# HVsense.net
KiCad netlist of a schematic drawn in Altium Designer
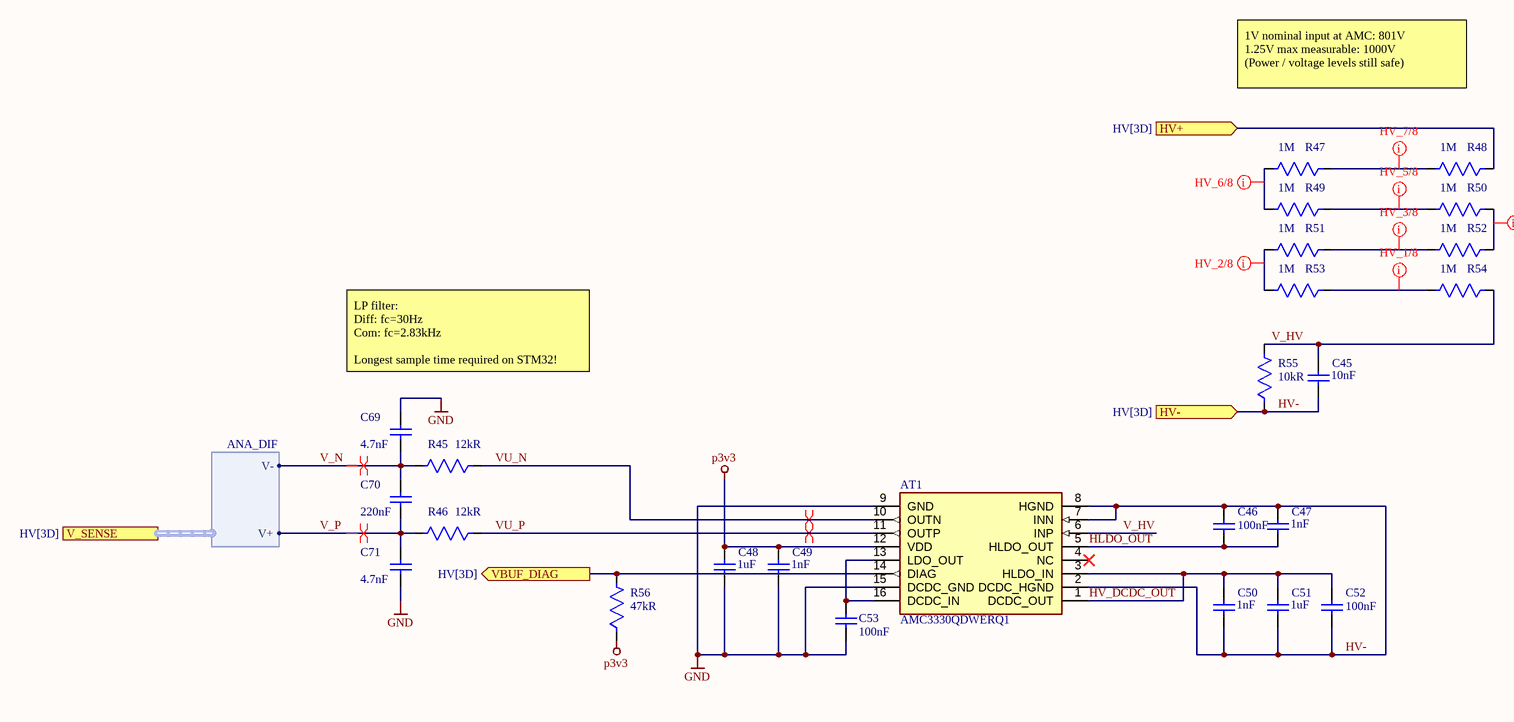
[diagram p0: HVsense.SchDoc]

(export (version "E")
  (design (tool "Eeschema 10.0.6"))
  (components
    (comp (ref "AT1")
      (value "AMC3330QDWERQ1")
      (footprint "SOIC127P1030X265-16N")
      (description "Attenuator or Isolator")
      (fields (field (name "MOUSER PART NUMBER") "595-AMC3330QDWERQ1"))
      (libsource (lib "FlexBMS_lib") (part "AMC3330QDWERQ1"))
    )
    (comp (ref "C45")
      (value "10nF")
      (footprint "WCAP-CSGP_0603_L1.6W0.8H0.8_Reflow")
      (description "GTT Standard 0603 non-polarized capacitor")
      (fields (field (name "JLCPCB PART #") "C57112") (field (name "Comment") "CAP 0603 10nF X7R"))
      (libsource (lib "Green Team Twente") (part "CAP_NONPOL_GENERIC"))
    )
    (comp (ref "C46")
      (value "100nF")
      (footprint "WCAP-CSGP_0603_L1.6W0.8H0.8_Reflow")
      (description "GTT Standard 0603 non-polarized capacitor")
      (fields (field (name "JLCPCB PART #") "C14663") (field (name "Comment") "CAP 0603 100nF X7R"))
      (libsource (lib "Green Team Twente") (part "CAP_NONPOL_GENERIC"))
    )
    (comp (ref "C47")
      (value "1nF")
      (footprint "WCAP-CSGP_0603_L1.6W0.8H0.8_Reflow")
      (description "GTT Standard 0603 non-polarized capacitor")
      (fields (field (name "JLCPCB PART #") "C1588") (field (name "Comment") "CAP 0603 1nF X7R"))
      (libsource (lib "Green Team Twente") (part "CAP_NONPOL_GENERIC"))
    )
    (comp (ref "C48")
      (value "1uF")
      (footprint "WCAP-CSGP_0603_L1.6W0.8H0.8_Reflow")
      (description "GTT Standard 0603 non-polarized capacitor")
      (fields (field (name "JLCPCB PART #") "C15849") (field (name "Comment") "CAP 0603 1uF X7R"))
      (libsource (lib "Green Team Twente") (part "CAP_NONPOL_GENERIC"))
    )
    (comp (ref "C49")
      (value "1nF")
      (footprint "WCAP-CSGP_0603_L1.6W0.8H0.8_Reflow")
      (description "GTT Standard 0603 non-polarized capacitor")
      (fields (field (name "JLCPCB PART #") "C1588") (field (name "Comment") "CAP 0603 1nF X7R"))
      (libsource (lib "Green Team Twente") (part "CAP_NONPOL_GENERIC"))
    )
    (comp (ref "C50")
      (value "1nF")
      (footprint "WCAP-CSGP_0603_L1.6W0.8H0.8_Reflow")
      (description "GTT Standard 0603 non-polarized capacitor")
      (fields (field (name "JLCPCB PART #") "C1588") (field (name "Comment") "CAP 0603 1nF X7R"))
      (libsource (lib "Green Team Twente") (part "CAP_NONPOL_GENERIC"))
    )
    (comp (ref "C51")
      (value "1uF")
      (footprint "WCAP-CSGP_0603_L1.6W0.8H0.8_Reflow")
      (description "GTT Standard 0603 non-polarized capacitor")
      (fields (field (name "JLCPCB PART #") "C15849") (field (name "Comment") "CAP 0603 1uF X7R"))
      (libsource (lib "Green Team Twente") (part "CAP_NONPOL_GENERIC"))
    )
    (comp (ref "C52")
      (value "100nF")
      (footprint "WCAP-CSGP_0603_L1.6W0.8H0.8_Reflow")
      (description "GTT Standard 0603 non-polarized capacitor")
      (fields (field (name "JLCPCB PART #") "C14663") (field (name "Comment") "CAP 0603 100nF X7R"))
      (libsource (lib "Green Team Twente") (part "CAP_NONPOL_GENERIC"))
    )
    (comp (ref "C53")
      (value "100nF")
      (footprint "WCAP-CSGP_0603_L1.6W0.8H0.8_Reflow")
      (description "GTT Standard 0603 non-polarized capacitor")
      (fields (field (name "JLCPCB PART #") "C14663") (field (name "Comment") "CAP 0603 100nF X7R"))
      (libsource (lib "Green Team Twente") (part "CAP_NONPOL_GENERIC"))
    )
    (comp (ref "C69")
      (value "4.7nF")
      (footprint "WCAP-CSGP_0402_L1W0.5H0.5")
      (description "GTT Standard 0402 non-polarized capacitor")
      (fields (field (name "JLCPCB PART #") "C1538") (field (name "Comment") "CAP 0402 4.7nF X7R"))
      (libsource (lib "Green Team Twente") (part "CAP_NONPOL_GENERIC"))
    )
    (comp (ref "C70")
      (value "220nF")
      (footprint "WCAP-CSGP_0402_L1W0.5H0.5")
      (description "GTT Standard 0402 non-polarized capacitor")
      (fields (field (name "JLCPCB PART #") "C16772") (field (name "Comment") "CAP 0402 220nF X7R"))
      (libsource (lib "Green Team Twente") (part "CAP_NONPOL_GENERIC"))
    )
    (comp (ref "C71")
      (value "4.7nF")
      (footprint "WCAP-CSGP_0402_L1W0.5H0.5")
      (description "GTT Standard 0402 non-polarized capacitor")
      (fields (field (name "JLCPCB PART #") "C1538") (field (name "Comment") "CAP 0402 4.7nF X7R"))
      (libsource (lib "Green Team Twente") (part "CAP_NONPOL_GENERIC"))
    )
    (comp (ref "R45")
      (value "12kR")
      (footprint "FP0402")
      (description "GTT Standard 0402 Resistor")
      (fields (field (name "TOLERANCE") "1%") (field (name "POWER") "62.5mW"))
      (libsource (lib "Green Team Twente") (part "RES_GENERIC"))
    )
    (comp (ref "R46")
      (value "12kR")
      (footprint "FP0402")
      (description "GTT Standard 0402 Resistor")
      (fields (field (name "TOLERANCE") "1%") (field (name "POWER") "62.5mW"))
      (libsource (lib "Green Team Twente") (part "RES_GENERIC"))
    )
    (comp (ref "R47")
      (value "1M")
      (footprint "RES_SM1206_YAGEORC_N")
      (description "GTT Standard 1206 Resistor")
      (fields (field (name "TOLERANCE") "1%") (field (name "POWER") "62.5mW"))
      (libsource (lib "Green Team Twente") (part "RES_GENERIC"))
    )
    (comp (ref "R48")
      (value "1M")
      (footprint "RES_SM1206_YAGEORC_N")
      (description "GTT Standard 1206 Resistor")
      (fields (field (name "TOLERANCE") "1%") (field (name "POWER") "62.5mW"))
      (libsource (lib "Green Team Twente") (part "RES_GENERIC"))
    )
    (comp (ref "R49")
      (value "1M")
      (footprint "RES_SM1206_YAGEORC_N")
      (description "GTT Standard 1206 Resistor")
      (fields (field (name "TOLERANCE") "1%") (field (name "POWER") "62.5mW"))
      (libsource (lib "Green Team Twente") (part "RES_GENERIC"))
    )
    (comp (ref "R50")
      (value "1M")
      (footprint "RES_SM1206_YAGEORC_N")
      (description "GTT Standard 1206 Resistor")
      (fields (field (name "TOLERANCE") "1%") (field (name "POWER") "62.5mW"))
      (libsource (lib "Green Team Twente") (part "RES_GENERIC"))
    )
    (comp (ref "R51")
      (value "1M")
      (footprint "RES_SM1206_YAGEORC_N")
      (description "GTT Standard 1206 Resistor")
      (fields (field (name "TOLERANCE") "1%") (field (name "POWER") "62.5mW"))
      (libsource (lib "Green Team Twente") (part "RES_GENERIC"))
    )
    (comp (ref "R52")
      (value "1M")
      (footprint "RES_SM1206_YAGEORC_N")
      (description "GTT Standard 1206 Resistor")
      (fields (field (name "TOLERANCE") "1%") (field (name "POWER") "62.5mW"))
      (libsource (lib "Green Team Twente") (part "RES_GENERIC"))
    )
    (comp (ref "R53")
      (value "1M")
      (footprint "RES_SM1206_YAGEORC_N")
      (description "GTT Standard 1206 Resistor")
      (fields (field (name "TOLERANCE") "1%") (field (name "POWER") "62.5mW"))
      (libsource (lib "Green Team Twente") (part "RES_GENERIC"))
    )
    (comp (ref "R54")
      (value "1M")
      (footprint "RES_SM1206_YAGEORC_N")
      (description "GTT Standard 1206 Resistor")
      (fields (field (name "TOLERANCE") "1%") (field (name "POWER") "62.5mW"))
      (libsource (lib "Green Team Twente") (part "RES_GENERIC"))
    )
    (comp (ref "R55")
      (value "10kR")
      (footprint "RES_SM0805_YAGEORC_N")
      (description "GTT Standard 0805 Resistor")
      (fields (field (name "POWER") "62.5mW") (field (name "TOLERANCE") "1%"))
      (libsource (lib "Green Team Twente") (part "RES_GENERIC"))
    )
    (comp (ref "R56")
      (value "47kR")
      (footprint "RES_SM0603_YAGEORC_N")
      (description "GTT Standard 0603 Resistor")
      (fields (field (name "POWER") "62.5mW") (field (name "TOLERANCE") "1%"))
      (libsource (lib "Green Team Twente") (part "RES_GENERIC"))
    )
  )
  (nets
    (net (code "2") (name "/HLDO_OUT") (class "Default")
      (node (ref "AT1") (pin "5") (pinfunction "HLDO_OUT_5") (pintype "power_in"))
      (node (ref "C46") (pin "2") (pinfunction "2_2") (pintype "passive"))
      (node (ref "C47") (pin "1") (pinfunction "1_1") (pintype "passive"))
    )
    (net (code "3") (name "/HV+") (class "Default")
      (node (ref "R48") (pin "1") (pinfunction "1_1") (pintype "passive"))
    )
    (net (code "4") (name "/HV-") (class "Default")
      (node (ref "AT1") (pin "2") (pinfunction "DCDC_HGND_2") (pintype "power_in"))
      (node (ref "AT1") (pin "7") (pinfunction "INN_7") (pintype "input"))
      (node (ref "AT1") (pin "8") (pinfunction "HGND_8") (pintype "power_in"))
      (node (ref "C45") (pin "1") (pinfunction "1_1") (pintype "passive"))
      (node (ref "C46") (pin "1") (pinfunction "1_1") (pintype "passive"))
      (node (ref "C47") (pin "2") (pinfunction "2_2") (pintype "passive"))
      (node (ref "C50") (pin "1") (pinfunction "1_1") (pintype "passive"))
      (node (ref "C51") (pin "1") (pinfunction "1_1") (pintype "passive"))
      (node (ref "C52") (pin "2") (pinfunction "2_2") (pintype "passive"))
      (node (ref "R55") (pin "1") (pinfunction "1_1") (pintype "passive"))
    )
    (net (code "5") (name "/HV_DCDC_OUT") (class "Default")
      (node (ref "AT1") (pin "1") (pinfunction "DCDC_OUT_1") (pintype "power_in"))
      (node (ref "AT1") (pin "3") (pinfunction "HLDO_IN_3") (pintype "power_in"))
      (node (ref "C50") (pin "2") (pinfunction "2_2") (pintype "passive"))
      (node (ref "C51") (pin "2") (pinfunction "2_2") (pintype "passive"))
      (node (ref "C52") (pin "1") (pinfunction "1_1") (pintype "passive"))
    )
    (net (code "6") (name "/VBUF_DIAG") (class "Default")
      (node (ref "AT1") (pin "14") (pinfunction "DIAG_14") (pintype "output"))
      (node (ref "R56") (pin "2") (pinfunction "2_2") (pintype "passive"))
    )
    (net (code "7") (name "/VU_N") (class "Default")
      (node (ref "AT1") (pin "10") (pinfunction "OUTN_10") (pintype "output"))
      (node (ref "R45") (pin "1") (pinfunction "1_1") (pintype "passive"))
    )
    (net (code "8") (name "/VU_P") (class "Default")
      (node (ref "AT1") (pin "11") (pinfunction "OUTP_11") (pintype "output"))
      (node (ref "R46") (pin "1") (pinfunction "1_1") (pintype "passive"))
    )
    (net (code "9") (name "/V_HV") (class "Default")
      (node (ref "AT1") (pin "6") (pinfunction "INP_6") (pintype "input"))
      (node (ref "C45") (pin "2") (pinfunction "2_2") (pintype "passive"))
      (node (ref "R54") (pin "1") (pinfunction "1_1") (pintype "passive"))
      (node (ref "R55") (pin "2") (pinfunction "2_2") (pintype "passive"))
    )
    (net (code "10") (name "/V_N") (class "Default")
      (node (ref "C69") (pin "1") (pinfunction "1_1") (pintype "passive"))
      (node (ref "C70") (pin "2") (pinfunction "2_2") (pintype "passive"))
      (node (ref "R45") (pin "2") (pinfunction "2_2") (pintype "passive"))
    )
    (net (code "11") (name "/V_P") (class "Default")
      (node (ref "C70") (pin "1") (pinfunction "1_1") (pintype "passive"))
      (node (ref "C71") (pin "2") (pinfunction "2_2") (pintype "passive"))
      (node (ref "R46") (pin "2") (pinfunction "2_2") (pintype "passive"))
    )
    (net (code "13") (name "GND") (class "Default")
      (node (ref "AT1") (pin "15") (pinfunction "DCDC_GND_15") (pintype "power_in"))
      (node (ref "AT1") (pin "9") (pinfunction "GND_9") (pintype "power_in"))
      (node (ref "C48") (pin "1") (pinfunction "1_1") (pintype "passive"))
      (node (ref "C49") (pin "1") (pinfunction "1_1") (pintype "passive"))
      (node (ref "C53") (pin "2") (pinfunction "2_2") (pintype "passive"))
      (node (ref "C69") (pin "2") (pinfunction "2_2") (pintype "passive"))
      (node (ref "C71") (pin "1") (pinfunction "1_1") (pintype "passive"))
    )
    (net (code "14") (name "Net-(AT1-DCDC_IN)") (class "Default")
      (node (ref "AT1") (pin "13") (pinfunction "LDO_OUT_13") (pintype "power_in"))
      (node (ref "AT1") (pin "16") (pinfunction "DCDC_IN_16") (pintype "power_in"))
      (node (ref "C53") (pin "1") (pinfunction "1_1") (pintype "passive"))
    )
    (net (code "15") (name "Net-(R47-Pad1)") (class "Default")
      (node (ref "R47") (pin "1") (pinfunction "1_1") (pintype "passive"))
      (node (ref "R48") (pin "2") (pinfunction "2_2") (pintype "passive"))
    )
    (net (code "16") (name "Net-(R47-Pad2)") (class "Default")
      (node (ref "R47") (pin "2") (pinfunction "2_2") (pintype "passive"))
      (node (ref "R49") (pin "2") (pinfunction "2_2") (pintype "passive"))
    )
    (net (code "17") (name "Net-(R49-Pad1)") (class "Default")
      (node (ref "R49") (pin "1") (pinfunction "1_1") (pintype "passive"))
      (node (ref "R50") (pin "2") (pinfunction "2_2") (pintype "passive"))
    )
    (net (code "18") (name "Net-(R50-Pad1)") (class "Default")
      (node (ref "R50") (pin "1") (pinfunction "1_1") (pintype "passive"))
      (node (ref "R52") (pin "1") (pinfunction "1_1") (pintype "passive"))
    )
    (net (code "19") (name "Net-(R51-Pad1)") (class "Default")
      (node (ref "R51") (pin "1") (pinfunction "1_1") (pintype "passive"))
      (node (ref "R52") (pin "2") (pinfunction "2_2") (pintype "passive"))
    )
    (net (code "20") (name "Net-(R51-Pad2)") (class "Default")
      (node (ref "R51") (pin "2") (pinfunction "2_2") (pintype "passive"))
      (node (ref "R53") (pin "2") (pinfunction "2_2") (pintype "passive"))
    )
    (net (code "21") (name "Net-(R53-Pad1)") (class "Default")
      (node (ref "R53") (pin "1") (pinfunction "1_1") (pintype "passive"))
      (node (ref "R54") (pin "2") (pinfunction "2_2") (pintype "passive"))
    )
    (net (code "22") (name "p3v3") (class "Default")
      (node (ref "AT1") (pin "12") (pinfunction "VDD_12") (pintype "power_in"))
      (node (ref "C48") (pin "2") (pinfunction "2_2") (pintype "passive"))
      (node (ref "C49") (pin "2") (pinfunction "2_2") (pintype "passive"))
      (node (ref "R56") (pin "1") (pinfunction "1_1") (pintype "passive"))
    )
    (net (code "23") (name "unconnected-(AT1-NC-Pad4)") (class "Default")
      (node (ref "AT1") (pin "4") (pinfunction "NC_4") (pintype "passive+no_connect"))
    )
  )
)
